# design.net
KiCad netlist of a schematic drawn in Altium Designer
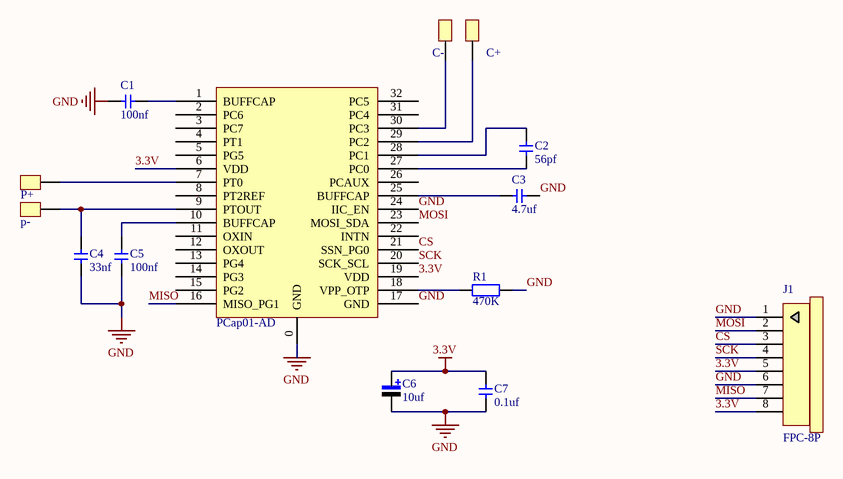
[diagram p0: 电容测量.SchDoc]

(export (version "E")
  (design (tool "Eeschema 10.0.6"))
  (components
    (comp (ref "C+")
      (value "pad")
      (footprint "pad_3x3")
      (description "焊盘接口")
      (libsource (lib "fszhang") (part "pad_3x3"))
    )
    (comp (ref "C-")
      (value "pad")
      (footprint "pad_3x3")
      (description "焊盘接口")
      (libsource (lib "fszhang") (part "pad_3x3"))
    )
    (comp (ref "C1")
      (value "100nf")
      (footprint "0603-2")
      (description "无极性电容")
      (fields (field (name "Comment") "Cap") (field (name "PUBLISHER") "Altium Limited"))
      (libsource (lib "fszhang") (part "Cap"))
    )
    (comp (ref "C2")
      (value "56pf")
      (footprint "0603-2")
      (description "无极性电容")
      (fields (field (name "Comment") "Cap") (field (name "PUBLISHER") "Altium Limited"))
      (libsource (lib "fszhang") (part "Cap"))
    )
    (comp (ref "C3")
      (value "4.7uf")
      (footprint "0603-2")
      (description "无极性电容")
      (fields (field (name "Comment") "Cap") (field (name "PUBLISHER") "Altium Limited"))
      (libsource (lib "fszhang") (part "Cap"))
    )
    (comp (ref "C4")
      (value "33nf")
      (footprint "0603-2")
      (description "无极性电容")
      (fields (field (name "Comment") "Cap") (field (name "PUBLISHER") "Altium Limited"))
      (libsource (lib "fszhang") (part "Cap"))
    )
    (comp (ref "C5")
      (value "100nf")
      (footprint "0603-2")
      (description "无极性电容")
      (fields (field (name "Comment") "Cap") (field (name "PUBLISHER") "Altium Limited"))
      (libsource (lib "fszhang") (part "Cap"))
    )
    (comp (ref "C6")
      (value "10uf")
      (footprint "CAP-3216")
      (description "极性电解电容")
      (fields (field (name "Comment") "Cap Pol") (field (name "PUBLISHER") "Altium Limited"))
      (libsource (lib "fszhang") (part "Cap Pol"))
    )
    (comp (ref "C7")
      (value "0.1uf")
      (footprint "0603-2")
      (description "无极性电容")
      (fields (field (name "Comment") "Cap") (field (name "PUBLISHER") "Altium Limited"))
      (libsource (lib "fszhang") (part "Cap"))
    )
    (comp (ref "J1")
      (value "FPC-8P")
      (footprint "FPC0.5-8P-C")
      (description "FPC排线连接器")
      (libsource (lib "fszhang") (part "FPC-8P"))
    )
    (comp (ref "P+")
      (value "pad")
      (footprint "pad_3x3")
      (description "焊盘接口")
      (libsource (lib "") (part "pad_3x3_1"))
    )
    (comp (ref "p-")
      (value "pad")
      (footprint "pad_3x3")
      (description "焊盘接口")
      (libsource (lib "") (part "pad_3x3_1"))
    )
    (comp (ref "R1")
      (value "470K")
      (footprint "0603-2")
      (description "贴片电阻")
      (fields (field (name "Comment") "Res1") (field (name "PUBLISHER") "Altium Limited"))
      (libsource (lib "fszhang") (part "Res1"))
    )
    (comp (ref "U1")
      (value "PCap01-AD")
      (footprint "QFN-32_5x5x05")
      (description "电容测量芯片")
      (libsource (lib "fszhang") (part "Pcap01AD"))
    )
  )
  (nets
    (net (code "1") (name "/CS") (class "Default")
      (node (ref "J1") (pin "3") (pinfunction "3_3") (pintype "passive"))
      (node (ref "U1") (pin "21") (pinfunction "SSN_PG0_21") (pintype "passive"))
    )
    (net (code "2") (name "/MISO") (class "Default")
      (node (ref "J1") (pin "7") (pinfunction "7_7") (pintype "passive"))
      (node (ref "U1") (pin "16") (pinfunction "MISO_PG1_16") (pintype "passive"))
    )
    (net (code "3") (name "/MOSI") (class "Default")
      (node (ref "J1") (pin "2") (pinfunction "2_2") (pintype "passive"))
      (node (ref "U1") (pin "23") (pinfunction "MOSI_SDA_23") (pintype "passive"))
    )
    (net (code "4") (name "/SCK") (class "Default")
      (node (ref "J1") (pin "4") (pinfunction "4_4") (pintype "passive"))
      (node (ref "U1") (pin "20") (pinfunction "SCK_SCL_20") (pintype "passive"))
    )
    (net (code "5") (name "3.3V") (class "Default")
      (node (ref "C6") (pin "1") (pinfunction "1_1") (pintype "passive"))
      (node (ref "C7") (pin "2") (pinfunction "2_2") (pintype "passive"))
      (node (ref "J1") (pin "5") (pinfunction "5_5") (pintype "passive"))
      (node (ref "J1") (pin "8") (pinfunction "8_8") (pintype "passive"))
      (node (ref "U1") (pin "19") (pinfunction "VDD_19") (pintype "passive"))
      (node (ref "U1") (pin "6") (pinfunction "VDD_6") (pintype "passive"))
    )
    (net (code "6") (name "GND") (class "Default")
      (node (ref "C1") (pin "2") (pinfunction "2_2") (pintype "passive"))
      (node (ref "C3") (pin "1") (pinfunction "1_1") (pintype "passive"))
      (node (ref "C4") (pin "2") (pinfunction "2_2") (pintype "passive"))
      (node (ref "C5") (pin "1") (pinfunction "1_1") (pintype "passive"))
      (node (ref "C6") (pin "2") (pinfunction "2_2") (pintype "passive"))
      (node (ref "C7") (pin "1") (pinfunction "1_1") (pintype "passive"))
      (node (ref "J1") (pin "1") (pinfunction "1_1") (pintype "passive"))
      (node (ref "J1") (pin "6") (pinfunction "6_6") (pintype "passive"))
      (node (ref "R1") (pin "2") (pinfunction "2_2") (pintype "passive"))
      (node (ref "U1") (pin "0") (pinfunction "GND_0") (pintype "passive"))
      (node (ref "U1") (pin "17") (pinfunction "GND_17") (pintype "passive"))
      (node (ref "U1") (pin "24") (pinfunction "IIC_EN_24") (pintype "passive"))
    )
    (net (code "7") (name "Net-(C1-Pad1)") (class "Default")
      (node (ref "C1") (pin "1") (pinfunction "1_1") (pintype "passive"))
      (node (ref "U1") (pin "1") (pinfunction "BUFFCAP_1") (pintype "passive"))
    )
    (net (code "8") (name "Net-(C3-Pad2)") (class "Default")
      (node (ref "C3") (pin "2") (pinfunction "2_2") (pintype "passive"))
      (node (ref "U1") (pin "25") (pinfunction "BUFFCAP_25") (pintype "passive"))
    )
    (net (code "9") (name "Net-(C5-Pad2)") (class "Default")
      (node (ref "C5") (pin "2") (pinfunction "2_2") (pintype "passive"))
      (node (ref "U1") (pin "10") (pinfunction "BUFFCAP_10") (pintype "passive"))
    )
    (net (code "10") (name "Net-(U1-PC0)") (class "Default")
      (node (ref "C2") (pin "1") (pinfunction "1_1") (pintype "passive"))
      (node (ref "U1") (pin "27") (pinfunction "PC0_27") (pintype "passive"))
    )
    (net (code "11") (name "Net-(U1-PC1)") (class "Default")
      (node (ref "C2") (pin "2") (pinfunction "2_2") (pintype "passive"))
      (node (ref "U1") (pin "28") (pinfunction "PC1_28") (pintype "passive"))
    )
    (net (code "12") (name "Net-(U1-PC2)") (class "Default")
      (node (ref "C+") (pin "1") (pinfunction "1_1") (pintype "passive"))
      (node (ref "U1") (pin "29") (pinfunction "PC2_29") (pintype "passive"))
    )
    (net (code "13") (name "Net-(U1-PC3)") (class "Default")
      (node (ref "C-") (pin "1") (pinfunction "1_1") (pintype "passive"))
      (node (ref "U1") (pin "30") (pinfunction "PC3_30") (pintype "passive"))
    )
    (net (code "14") (name "Net-(U1-PT0)") (class "Default")
      (node (ref "P+") (pin "1") (pinfunction "1_1") (pintype "passive"))
      (node (ref "U1") (pin "7") (pinfunction "PT0_7") (pintype "passive"))
    )
    (net (code "15") (name "Net-(U1-PTOUT)") (class "Default")
      (node (ref "C4") (pin "1") (pinfunction "1_1") (pintype "passive"))
      (node (ref "U1") (pin "9") (pinfunction "PTOUT_9") (pintype "passive"))
      (node (ref "p-") (pin "1") (pinfunction "1_1") (pintype "passive"))
    )
    (net (code "16") (name "Net-(U1-VPP_OTP)") (class "Default")
      (node (ref "R1") (pin "1") (pinfunction "1_1") (pintype "passive"))
      (node (ref "U1") (pin "18") (pinfunction "VPP_OTP_18") (pintype "passive"))
    )
    (net (code "17") (name "unconnected-(U1-INTN-Pad22)") (class "Default")
      (node (ref "U1") (pin "22") (pinfunction "INTN_22") (pintype "passive"))
    )
    (net (code "18") (name "unconnected-(U1-OXIN-Pad11)") (class "Default")
      (node (ref "U1") (pin "11") (pinfunction "OXIN_11") (pintype "passive"))
    )
    (net (code "19") (name "unconnected-(U1-OXOUT-Pad12)") (class "Default")
      (node (ref "U1") (pin "12") (pinfunction "OXOUT_12") (pintype "passive"))
    )
    (net (code "20") (name "unconnected-(U1-PC4-Pad31)") (class "Default")
      (node (ref "U1") (pin "31") (pinfunction "PC4_31") (pintype "passive"))
    )
    (net (code "21") (name "unconnected-(U1-PC5-Pad32)") (class "Default")
      (node (ref "U1") (pin "32") (pinfunction "PC5_32") (pintype "passive"))
    )
    (net (code "22") (name "unconnected-(U1-PC6-Pad2)") (class "Default")
      (node (ref "U1") (pin "2") (pinfunction "PC6_2") (pintype "passive"))
    )
    (net (code "23") (name "unconnected-(U1-PC7-Pad3)") (class "Default")
      (node (ref "U1") (pin "3") (pinfunction "PC7_3") (pintype "passive"))
    )
    (net (code "24") (name "unconnected-(U1-PCAUX-Pad26)") (class "Default")
      (node (ref "U1") (pin "26") (pinfunction "PCAUX_26") (pintype "passive"))
    )
    (net (code "25") (name "unconnected-(U1-PG2-Pad15)") (class "Default")
      (node (ref "U1") (pin "15") (pinfunction "PG2_15") (pintype "passive"))
    )
    (net (code "26") (name "unconnected-(U1-PG3-Pad14)") (class "Default")
      (node (ref "U1") (pin "14") (pinfunction "PG3_14") (pintype "passive"))
    )
    (net (code "27") (name "unconnected-(U1-PG4-Pad13)") (class "Default")
      (node (ref "U1") (pin "13") (pinfunction "PG4_13") (pintype "passive"))
    )
    (net (code "28") (name "unconnected-(U1-PG5-Pad5)") (class "Default")
      (node (ref "U1") (pin "5") (pinfunction "PG5_5") (pintype "passive"))
    )
    (net (code "29") (name "unconnected-(U1-PT1-Pad4)") (class "Default")
      (node (ref "U1") (pin "4") (pinfunction "PT1_4") (pintype "passive"))
    )
    (net (code "30") (name "unconnected-(U1-PT2REF-Pad8)") (class "Default")
      (node (ref "U1") (pin "8") (pinfunction "PT2REF_8") (pintype "passive"))
    )
  )
)
